# Sch.net
KiCad netlist of a schematic drawn in Altium Designer
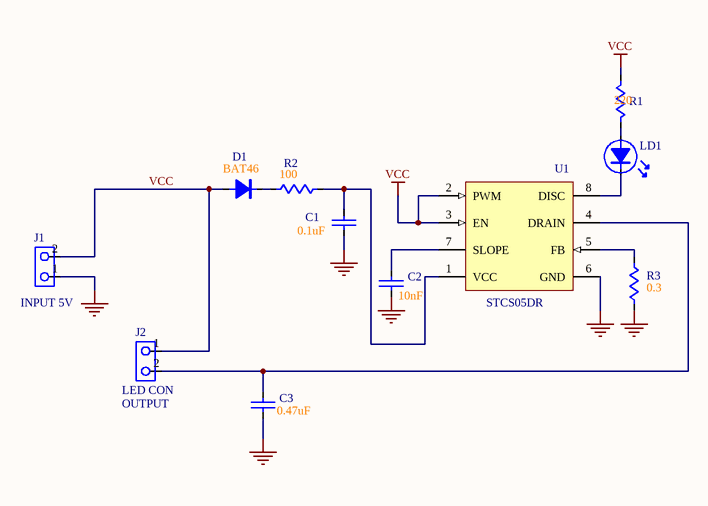
[diagram p0: Sch.SchDoc]

(export (version "E")
  (design (tool "Eeschema 10.0.6"))
  (components
    (comp (ref "C1")
      (value "CAPNP")
      (footprint "0805 SMD CAP")
      (description "Capacitor")
      (libsource (lib "SMPS1") (part "CAPNP"))
    )
    (comp (ref "C2")
      (value "CAPNP")
      (footprint "0805 SMD CAP")
      (description "Capacitor")
      (libsource (lib "SMPS1") (part "CAPNP"))
    )
    (comp (ref "C3")
      (value "CAPNP")
      (footprint "0805 SMD CAP")
      (description "Capacitor")
      (libsource (lib "SMPS1") (part "CAPNP"))
    )
    (comp (ref "D1")
      (value "schottky diode")
      (footprint "BAT46ZFILM DIODE")
      (description "Diode")
      (libsource (lib "SMPS1") (part "D-1"))
    )
    (comp (ref "J1")
      (value "INPUT 5V")
      (footprint "CONN-5083-2P")
      (description "Connector")
      (libsource (lib "SMPS1") (part "CONN2"))
    )
    (comp (ref "J2")
      (value "LED CON")
      (footprint "CONN-5083-2P")
      (description "Connector")
      (libsource (lib "SMPS1") (part "CONN2"))
    )
    (comp (ref "LD1")
      (value "Osram 0805 SMD GRN LED")
      (footprint "LED3MM")
      (libsource (lib "SMPS1") (part "LED-1"))
    )
    (comp (ref "R1") (value "RES1") (footprint "SMD1206N") (libsource (lib "SMPS1") (part "RES1")))
    (comp (ref "R2") (value "RES1") (footprint "SMD1206N") (libsource (lib "SMPS1") (part "RES1")))
    (comp (ref "R3") (value "RES1") (footprint "0805 SMD RES") (libsource (lib "SMPS1") (part "RES1")))
    (comp (ref "U1")
      (value "STCS05DR")
      (footprint "SO8_M")
      (description "0.5 A Max Constant Current LED Driver, 8-Pin SO, Tape and Reel")
      (libsource (lib "SMPSIC") (part "STCS05ADR"))
    )
  )
  (nets
    (net (code "1") (name "GND") (class "Default")
      (node (ref "C1") (pin "2") (pinfunction "2_2") (pintype "passive"))
      (node (ref "C2") (pin "2") (pinfunction "2_2") (pintype "passive"))
      (node (ref "C3") (pin "2") (pinfunction "2_2") (pintype "passive"))
      (node (ref "J1") (pin "1") (pinfunction "1_1") (pintype "passive"))
      (node (ref "R3") (pin "1") (pinfunction "1_1") (pintype "passive"))
      (node (ref "U1") (pin "6") (pinfunction "GND_6") (pintype "power_in"))
    )
    (net (code "2") (name "Net-(D1-PadK)") (class "Default")
      (node (ref "D1") (pin "K") (pinfunction "K_K") (pintype "passive"))
      (node (ref "R2") (pin "1") (pinfunction "1_1") (pintype "passive"))
    )
    (net (code "3") (name "Net-(LD1-PadA)") (class "Default")
      (node (ref "LD1") (pin "A") (pinfunction "A_A") (pintype "passive"))
      (node (ref "R1") (pin "1") (pinfunction "1_1") (pintype "passive"))
    )
    (net (code "4") (name "Net-(U1-DISC)") (class "Default")
      (node (ref "LD1") (pin "K") (pinfunction "K_K") (pintype "passive"))
      (node (ref "U1") (pin "8") (pinfunction "DISC_8") (pintype "open_collector"))
    )
    (net (code "5") (name "Net-(U1-DRAIN)") (class "Default")
      (node (ref "C3") (pin "1") (pinfunction "1_1") (pintype "passive"))
      (node (ref "J2") (pin "2") (pinfunction "2_2") (pintype "passive"))
      (node (ref "U1") (pin "4") (pinfunction "DRAIN_4") (pintype "open_collector"))
    )
    (net (code "6") (name "Net-(U1-FB)") (class "Default")
      (node (ref "R3") (pin "2") (pinfunction "2_2") (pintype "passive"))
      (node (ref "U1") (pin "5") (pinfunction "FB_5") (pintype "input"))
    )
    (net (code "7") (name "Net-(U1-SLOPE)") (class "Default")
      (node (ref "C2") (pin "1") (pinfunction "1_1") (pintype "passive"))
      (node (ref "U1") (pin "7") (pinfunction "SLOPE_7") (pintype "passive"))
    )
    (net (code "8") (name "Net-(U1-VCC)") (class "Default")
      (node (ref "C1") (pin "1") (pinfunction "1_1") (pintype "passive"))
      (node (ref "R2") (pin "2") (pinfunction "2_2") (pintype "passive"))
      (node (ref "U1") (pin "1") (pinfunction "VCC_1") (pintype "power_in"))
    )
    (net (code "9") (name "VCC") (class "Default")
      (node (ref "D1") (pin "A") (pinfunction "A_A") (pintype "passive"))
      (node (ref "J1") (pin "2") (pinfunction "2_2") (pintype "passive"))
      (node (ref "J2") (pin "1") (pinfunction "1_1") (pintype "passive"))
      (node (ref "R1") (pin "2") (pinfunction "2_2") (pintype "passive"))
      (node (ref "U1") (pin "2") (pinfunction "PWM_2") (pintype "input"))
      (node (ref "U1") (pin "3") (pinfunction "EN_3") (pintype "input"))
    )
  )
)
